# L-BAND_V2_0.net
KiCad netlist of a schematic drawn in Altium Designer
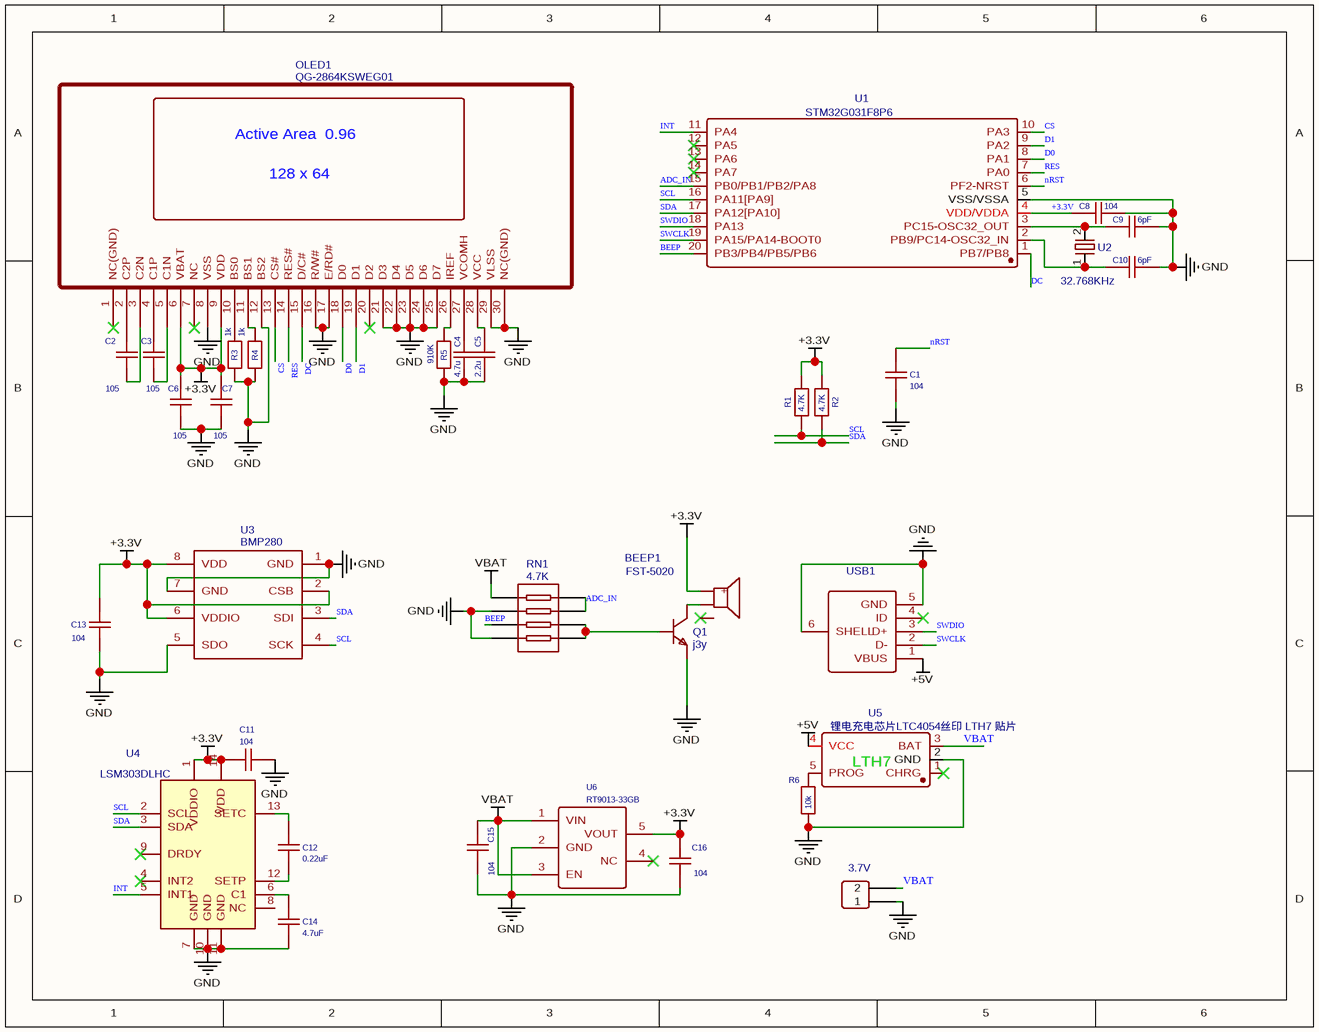
[diagram p0: L-BAND_V2_0.schdoc]

(export (version "E")
  (design (tool "Eeschema 10.0.6"))
  (components
    (comp (ref "3.7V")
      (value "3.7V 400mAH")
      (fields
        (field (name "BOM_MANUFACTURER PART") "2.54mm 1*2P")
        (field (name "BOM_SUPPLIER PART") "C36717")
      )
      (libsource (lib "altium-import") (part "root_2_3.7V 400mAH_"))
    )
    (comp (ref "BEEP1")
      (value "FST-5020")
      (fields (field (name "BOM_SUPPLIER PART") "C391029") (field (name "CONTRIBUTOR") "LCSC"))
      (libsource (lib "altium-import") (part "root_0_FST-5020_"))
    )
    (comp (ref "C1")
      (value "104")
      (fields (field (name "CONTRIBUTOR") "LCEDA_Lib"))
      (libsource (lib "altium-import") (part "root_1_104_"))
    )
    (comp (ref "C2")
      (value "105")
      (fields (field (name "CONTRIBUTOR") "LCEDA_Lib"))
      (libsource (lib "altium-import") (part "root_1_105_"))
    )
    (comp (ref "C3")
      (value "105")
      (fields (field (name "CONTRIBUTOR") "LCEDA_Lib"))
      (libsource (lib "altium-import") (part "root_1_105_"))
    )
    (comp (ref "C4")
      (value "4.7u")
      (fields (field (name "CONTRIBUTOR") "LCEDA_Lib"))
      (libsource (lib "altium-import") (part "root_1_4.7u_"))
    )
    (comp (ref "C5")
      (value "2.2u")
      (fields (field (name "CONTRIBUTOR") "LCEDA_Lib"))
      (libsource (lib "altium-import") (part "root_1_2.2u_"))
    )
    (comp (ref "C6")
      (value "105")
      (fields (field (name "CONTRIBUTOR") "LCEDA_Lib"))
      (libsource (lib "altium-import") (part "root_1_105_"))
    )
    (comp (ref "C7")
      (value "105")
      (fields (field (name "CONTRIBUTOR") "LCEDA_Lib"))
      (libsource (lib "altium-import") (part "root_1_105_"))
    )
    (comp (ref "C8")
      (value "104")
      (fields (field (name "CONTRIBUTOR") "LCEDA_Lib"))
      (libsource (lib "altium-import") (part "root_2_104_"))
    )
    (comp (ref "C9")
      (value "6pF")
      (fields (field (name "CONTRIBUTOR") "LCEDA_Lib"))
      (libsource (lib "altium-import") (part "root_2_6pF_"))
    )
    (comp (ref "C10")
      (value "6pF")
      (fields (field (name "CONTRIBUTOR") "LCEDA_Lib"))
      (libsource (lib "altium-import") (part "root_2_6pF_"))
    )
    (comp (ref "C11")
      (value "104")
      (fields (field (name "CONTRIBUTOR") "LCEDA_Lib"))
      (libsource (lib "altium-import") (part "root_2_104_"))
    )
    (comp (ref "C12")
      (value "0.22uF")
      (fields (field (name "CONTRIBUTOR") "LCEDA_Lib"))
      (libsource (lib "altium-import") (part "root_1_0.22uF_"))
    )
    (comp (ref "C13")
      (value "104")
      (fields (field (name "CONTRIBUTOR") "LCEDA_Lib"))
      (libsource (lib "altium-import") (part "root_1_104_"))
    )
    (comp (ref "C14")
      (value "4.7uF")
      (fields (field (name "CONTRIBUTOR") "LCEDA_Lib"))
      (libsource (lib "altium-import") (part "root_3_4.7uF_"))
    )
    (comp (ref "C15")
      (value "104")
      (fields (field (name "CONTRIBUTOR") "LCEDA_Lib"))
      (libsource (lib "altium-import") (part "root_1_104_"))
    )
    (comp (ref "C16")
      (value "104")
      (fields (field (name "CONTRIBUTOR") "LCEDA_Lib"))
      (libsource (lib "altium-import") (part "root_1_104_"))
    )
    (comp (ref "OLED1")
      (value "QG-2864KSWEG01")
      (fields (field (name "BOM_SUPPLIER PART") "C85007"))
      (libsource (lib "altium-import") (part "root_0_QG-2864KSWEG01_"))
    )
    (comp (ref "Q1")
      (value "j3y")
      (fields
        (field (name "BOM_SUPPLIER PART") "C364312")
        (field (name "BOM_MANUFACTURER PART") "S8050-J3Y")
        (field (name "CONTRIBUTOR") "youshutian")
      )
      (libsource (lib "altium-import") (part "root_0_j3y_"))
    )
    (comp (ref "R1")
      (value "4.7K")
      (fields (field (name "CONTRIBUTOR") "LCEDA_Lib"))
      (libsource (lib "altium-import") (part "root_3_4.7K_"))
    )
    (comp (ref "R2")
      (value "4.7K")
      (fields (field (name "CONTRIBUTOR") "LCEDA_Lib"))
      (libsource (lib "altium-import") (part "root_3_4.7K_"))
    )
    (comp (ref "R3")
      (value "1k")
      (fields (field (name "CONTRIBUTOR") "LCEDA_Lib"))
      (libsource (lib "altium-import") (part "root_3_1k_"))
    )
    (comp (ref "R4")
      (value "1k")
      (fields (field (name "CONTRIBUTOR") "LCEDA_Lib"))
      (libsource (lib "altium-import") (part "root_3_1k_"))
    )
    (comp (ref "R5")
      (value "910K")
      (fields (field (name "CONTRIBUTOR") "LCEDA_Lib"))
      (libsource (lib "altium-import") (part "root_3_910K_"))
    )
    (comp (ref "R6")
      (value "10k")
      (fields (field (name "CONTRIBUTOR") "LCEDA_Lib"))
      (libsource (lib "altium-import") (part "root_3_10k_"))
    )
    (comp (ref "RN1")
      (value "4.7K")
      (fields
        (field (name "BOM_MANUFACTURER PART") "RC-ML08W103JT")
        (field (name "BOM_SUPPLIER PART") "C69593")
        (field (name "CONTRIBUTOR") "LCSC")
      )
      (libsource (lib "altium-import") (part "root_1_4.7K_"))
    )
    (comp (ref "U1")
      (value "STM32G031F8P6")
      (fields (field (name "BOM_SUPPLIER PART") "C529334") (field (name "CONTRIBUTOR") "LCSC"))
      (libsource (lib "altium-import") (part "root_2_STM32G031F8P6_"))
    )
    (comp (ref "U2")
      (value "32.768KHz")
      (fields
        (field (name "BOM_SUPPLIER PART") "C1986919")
        (field (name "BOM_MANUFACTURER PART") "FC-135 32.7680KA-K0")
        (field (name "CONTRIBUTOR") "LCSC")
      )
      (libsource (lib "altium-import") (part "root_1_32.768KHz_"))
    )
    (comp (ref "U3")
      (value "BMP280")
      (fields (field (name "BOM_SUPPLIER PART") "C83291"))
      (libsource (lib "altium-import") (part "root_0_BMP280_"))
    )
    (comp (ref "U4")
      (value "LSM303DLHC")
      (fields (field (name "CONTRIBUTOR") "KiCAD"))
      (libsource (lib "altium-import") (part "root_0_LSM303DLHC_"))
    )
    (comp (ref "U5")
      (value "锂电充电芯片LTC4054丝印 LTH7 贴片")
      (fields
        (field (name "BOM_MANUFACTURER PART") "XT4054K421MR-G")
        (field (name "CONTRIBUTOR") "wudigaogao")
      )
      (libsource (lib "altium-import") (part "root_2_锂电充电芯片LTC4054丝印 LTH7 贴片_"))
    )
    (comp (ref "U6")
      (value "RT9013-33GB")
      (fields (field (name "BOM_SUPPLIER PART") "C47773"))
      (libsource (lib "altium-import") (part "root_0_RT9013-33GB_"))
    )
    (comp (ref "USB1")
      (value "MICRO XNJ ZB")
      (fields (field (name "BOM_SUPPLIER PART") "C668587") (field (name "CONTRIBUTOR") "LCSC"))
      (libsource (lib "altium-import") (part "root_2_MICRO XNJ ZB_"))
    )
  )
  (nets
    (net (code "1") (name "+3.3V") (class "Default")
      (node (ref "BEEP1") (pin "1") (pinfunction "+_1") (pintype "passive"))
      (node (ref "C11") (pin "2") (pinfunction "2_2") (pintype "passive"))
      (node (ref "C13") (pin "2") (pinfunction "2_2") (pintype "passive"))
      (node (ref "C16") (pin "2") (pinfunction "2_2") (pintype "passive"))
      (node (ref "C6") (pin "2") (pinfunction "2_2") (pintype "passive"))
      (node (ref "C7") (pin "2") (pinfunction "2_2") (pintype "passive"))
      (node (ref "C8") (pin "2") (pinfunction "2_2") (pintype "passive"))
      (node (ref "OLED1") (pin "6") (pinfunction "VBAT_6") (pintype "passive"))
      (node (ref "OLED1") (pin "9") (pinfunction "VDD_9") (pintype "passive"))
      (node (ref "R1") (pin "1") (pinfunction "1_1") (pintype "passive"))
      (node (ref "R2") (pin "1") (pinfunction "1_1") (pintype "passive"))
      (node (ref "U1") (pin "4") (pinfunction "VDD/VDDA_4") (pintype "passive"))
      (node (ref "U3") (pin "2") (pinfunction "CSB_2") (pintype "passive"))
      (node (ref "U3") (pin "6") (pinfunction "VDDIO_6") (pintype "passive"))
      (node (ref "U3") (pin "8") (pinfunction "VDD_8") (pintype "passive"))
      (node (ref "U4") (pin "1") (pinfunction "VDDIO_1") (pintype "passive"))
      (node (ref "U4") (pin "14") (pinfunction "VDD_14") (pintype "passive"))
      (node (ref "U6") (pin "5") (pinfunction "VOUT_5") (pintype "passive"))
    )
    (net (code "2") (name "+5V") (class "Default")
      (node (ref "U5") (pin "4") (pinfunction "VCC_4") (pintype "passive"))
      (node (ref "USB1") (pin "1") (pinfunction "VBUS_1") (pintype "passive"))
    )
    (net (code "3") (name "/ADC_IN") (class "Default")
      (node (ref "RN1") (pin "3") (pinfunction "3_3") (pintype "passive"))
      (node (ref "RN1") (pin "4") (pinfunction "4_4") (pintype "passive"))
      (node (ref "U1") (pin "15") (pinfunction "PB0/PB1/PB2/PA8_15") (pintype "passive"))
    )
    (net (code "4") (name "/BEEP") (class "Default")
      (node (ref "RN1") (pin "7") (pinfunction "7_7") (pintype "passive"))
      (node (ref "U1") (pin "20") (pinfunction "PB3/PB4/PB5/PB6_20") (pintype "passive"))
    )
    (net (code "5") (name "/CS") (class "Default")
      (node (ref "OLED1") (pin "13") (pinfunction "CS#_13") (pintype "passive"))
      (node (ref "U1") (pin "10") (pinfunction "PA3_10") (pintype "passive"))
    )
    (net (code "6") (name "/D0") (class "Default")
      (node (ref "OLED1") (pin "18") (pinfunction "D0_18") (pintype "passive"))
      (node (ref "U1") (pin "8") (pinfunction "PA1_8") (pintype "passive"))
    )
    (net (code "7") (name "/D1") (class "Default")
      (node (ref "OLED1") (pin "19") (pinfunction "D1_19") (pintype "passive"))
      (node (ref "U1") (pin "9") (pinfunction "PA2_9") (pintype "passive"))
    )
    (net (code "8") (name "/DC") (class "Default")
      (node (ref "OLED1") (pin "15") (pinfunction "D/C#_15") (pintype "passive"))
      (node (ref "U1") (pin "1") (pinfunction "PB7/PB8_1") (pintype "passive"))
    )
    (net (code "9") (name "/INT") (class "Default")
      (node (ref "U1") (pin "11") (pinfunction "PA4_11") (pintype "passive"))
      (node (ref "U4") (pin "5") (pinfunction "INT1_5") (pintype "passive"))
    )
    (net (code "10") (name "/RES") (class "Default")
      (node (ref "OLED1") (pin "14") (pinfunction "RES#_14") (pintype "passive"))
      (node (ref "U1") (pin "7") (pinfunction "PA0_7") (pintype "passive"))
    )
    (net (code "11") (name "/SCL") (class "Default")
      (node (ref "R1") (pin "2") (pinfunction "2_2") (pintype "passive"))
      (node (ref "U1") (pin "16") (pinfunction "PA11[PA9]_16") (pintype "passive"))
      (node (ref "U3") (pin "4") (pinfunction "SCK_4") (pintype "passive"))
      (node (ref "U4") (pin "2") (pinfunction "SCL_2") (pintype "passive"))
    )
    (net (code "12") (name "/SDA") (class "Default")
      (node (ref "R2") (pin "2") (pinfunction "2_2") (pintype "passive"))
      (node (ref "U1") (pin "17") (pinfunction "PA12[PA10]_17") (pintype "passive"))
      (node (ref "U3") (pin "3") (pinfunction "SDI_3") (pintype "passive"))
      (node (ref "U4") (pin "3") (pinfunction "SDA_3") (pintype "passive"))
    )
    (net (code "13") (name "/SWCLK") (class "Default")
      (node (ref "U1") (pin "19") (pinfunction "PA15/PA14-BOOT0_19") (pintype "passive"))
      (node (ref "USB1") (pin "2") (pinfunction "D-_2") (pintype "passive"))
    )
    (net (code "14") (name "/SWDIO") (class "Default")
      (node (ref "U1") (pin "18") (pinfunction "PA13_18") (pintype "passive"))
      (node (ref "USB1") (pin "3") (pinfunction "D+_3") (pintype "passive"))
    )
    (net (code "15") (name "/nRST") (class "Default")
      (node (ref "C1") (pin "2") (pinfunction "2_2") (pintype "passive"))
      (node (ref "U1") (pin "6") (pinfunction "PF2-NRST_6") (pintype "passive"))
    )
    (net (code "16") (name "GND") (class "Default")
      (node (ref "3.7V") (pin "1") (pinfunction "1_1") (pintype "passive"))
      (node (ref "C1") (pin "1") (pinfunction "1_1") (pintype "passive"))
      (node (ref "C10") (pin "1") (pinfunction "1_1") (pintype "passive"))
      (node (ref "C11") (pin "1") (pinfunction "1_1") (pintype "passive"))
      (node (ref "C13") (pin "1") (pinfunction "1_1") (pintype "passive"))
      (node (ref "C14") (pin "2") (pinfunction "2_2") (pintype "passive"))
      (node (ref "C15") (pin "1") (pinfunction "1_1") (pintype "passive"))
      (node (ref "C16") (pin "1") (pinfunction "1_1") (pintype "passive"))
      (node (ref "C4") (pin "1") (pinfunction "1_1") (pintype "passive"))
      (node (ref "C5") (pin "1") (pinfunction "1_1") (pintype "passive"))
      (node (ref "C6") (pin "1") (pinfunction "1_1") (pintype "passive"))
      (node (ref "C7") (pin "1") (pinfunction "1_1") (pintype "passive"))
      (node (ref "C8") (pin "1") (pinfunction "1_1") (pintype "passive"))
      (node (ref "C9") (pin "1") (pinfunction "1_1") (pintype "passive"))
      (node (ref "OLED1") (pin "12") (pinfunction "BS2_12") (pintype "passive"))
      (node (ref "OLED1") (pin "16") (pinfunction "R/W#_16") (pintype "passive"))
      (node (ref "OLED1") (pin "17") (pinfunction "E/RD#_17") (pintype "passive"))
      (node (ref "OLED1") (pin "21") (pinfunction "D3_21") (pintype "passive"))
      (node (ref "OLED1") (pin "22") (pinfunction "D4_22") (pintype "passive"))
      (node (ref "OLED1") (pin "23") (pinfunction "D5_23") (pintype "passive"))
      (node (ref "OLED1") (pin "24") (pinfunction "D6_24") (pintype "passive"))
      (node (ref "OLED1") (pin "25") (pinfunction "D7_25") (pintype "passive"))
      (node (ref "OLED1") (pin "29") (pinfunction "VLSS_29") (pintype "passive"))
      (node (ref "OLED1") (pin "30") (pinfunction "NC(GND)_30") (pintype "passive"))
      (node (ref "OLED1") (pin "8") (pinfunction "VSS_8") (pintype "passive"))
      (node (ref "Q1") (pin "2") (pinfunction "E_2") (pintype "passive"))
      (node (ref "R3") (pin "2") (pinfunction "2_2") (pintype "passive"))
      (node (ref "R4") (pin "2") (pinfunction "2_2") (pintype "passive"))
      (node (ref "R5") (pin "2") (pinfunction "2_2") (pintype "passive"))
      (node (ref "R6") (pin "2") (pinfunction "2_2") (pintype "passive"))
      (node (ref "RN1") (pin "6") (pinfunction "6_6") (pintype "passive"))
      (node (ref "RN1") (pin "8") (pinfunction "8_8") (pintype "passive"))
      (node (ref "U1") (pin "5") (pinfunction "VSS/VSSA_5") (pintype "passive"))
      (node (ref "U3") (pin "1") (pinfunction "GND_1") (pintype "passive"))
      (node (ref "U3") (pin "5") (pinfunction "SDO_5") (pintype "passive"))
      (node (ref "U3") (pin "7") (pinfunction "GND_7") (pintype "passive"))
      (node (ref "U4") (pin "10") (pinfunction "GND_10") (pintype "passive"))
      (node (ref "U4") (pin "11") (pinfunction "GND_11") (pintype "passive"))
      (node (ref "U4") (pin "7") (pinfunction "GND_7") (pintype "passive"))
      (node (ref "U5") (pin "2") (pinfunction "GND_2") (pintype "passive"))
      (node (ref "U6") (pin "2") (pinfunction "GND_2") (pintype "passive"))
      (node (ref "USB1") (pin "5") (pinfunction "GND_5") (pintype "passive"))
      (node (ref "USB1") (pin "6") (pinfunction "SHELL_6") (pintype "passive"))
    )
    (net (code "17") (name "Net-(OLED1-BS0)") (class "Default")
      (node (ref "OLED1") (pin "10") (pinfunction "BS0_10") (pintype "passive"))
      (node (ref "R3") (pin "1") (pinfunction "1_1") (pintype "passive"))
    )
    (net (code "18") (name "Net-(OLED1-BS1)") (class "Default")
      (node (ref "OLED1") (pin "11") (pinfunction "BS1_11") (pintype "passive"))
      (node (ref "R4") (pin "1") (pinfunction "1_1") (pintype "passive"))
    )
    (net (code "19") (name "Net-(OLED1-C1N)") (class "Default")
      (node (ref "C3") (pin "1") (pinfunction "1_1") (pintype "passive"))
      (node (ref "OLED1") (pin "5") (pinfunction "C1N_5") (pintype "passive"))
    )
    (net (code "20") (name "Net-(OLED1-C1P)") (class "Default")
      (node (ref "C3") (pin "2") (pinfunction "2_2") (pintype "passive"))
      (node (ref "OLED1") (pin "4") (pinfunction "C1P_4") (pintype "passive"))
    )
    (net (code "21") (name "Net-(OLED1-C2N)") (class "Default")
      (node (ref "C2") (pin "1") (pinfunction "1_1") (pintype "passive"))
      (node (ref "OLED1") (pin "3") (pinfunction "C2N_3") (pintype "passive"))
    )
    (net (code "22") (name "Net-(OLED1-C2P)") (class "Default")
      (node (ref "C2") (pin "2") (pinfunction "2_2") (pintype "passive"))
      (node (ref "OLED1") (pin "2") (pinfunction "C2P_2") (pintype "passive"))
    )
    (net (code "23") (name "Net-(OLED1-IREF)") (class "Default")
      (node (ref "OLED1") (pin "26") (pinfunction "IREF_26") (pintype "passive"))
      (node (ref "R5") (pin "1") (pinfunction "1_1") (pintype "passive"))
    )
    (net (code "24") (name "Net-(OLED1-VCC)") (class "Default")
      (node (ref "C5") (pin "2") (pinfunction "2_2") (pintype "passive"))
      (node (ref "OLED1") (pin "28") (pinfunction "VCC_28") (pintype "passive"))
    )
    (net (code "25") (name "Net-(OLED1-VCOMH)") (class "Default")
      (node (ref "C4") (pin "2") (pinfunction "2_2") (pintype "passive"))
      (node (ref "OLED1") (pin "27") (pinfunction "VCOMH_27") (pintype "passive"))
    )
    (net (code "26") (name "Net-(Q1-B)") (class "Default")
      (node (ref "Q1") (pin "1") (pinfunction "B_1") (pintype "passive"))
      (node (ref "RN1") (pin "1") (pinfunction "1_1") (pintype "passive"))
      (node (ref "RN1") (pin "2") (pinfunction "2_2") (pintype "passive"))
    )
    (net (code "27") (name "Net-(Q1-C)") (class "Default")
      (node (ref "BEEP1") (pin "2") (pinfunction "2_2") (pintype "passive"))
      (node (ref "Q1") (pin "3") (pinfunction "C_3") (pintype "passive"))
    )
    (net (code "28") (name "Net-(U1-PB9{slash}PC14-OSC32_IN)") (class "Default")
      (node (ref "C10") (pin "2") (pinfunction "2_2") (pintype "passive"))
      (node (ref "U1") (pin "2") (pinfunction "PB9/PC14-OSC32_IN_2") (pintype "passive"))
      (node (ref "U2") (pin "1") (pinfunction "1_1") (pintype "passive"))
    )
    (net (code "29") (name "Net-(U1-PC15-OSC32_OUT)") (class "Default")
      (node (ref "C9") (pin "2") (pinfunction "2_2") (pintype "passive"))
      (node (ref "U1") (pin "3") (pinfunction "PC15-OSC32_OUT_3") (pintype "passive"))
      (node (ref "U2") (pin "2") (pinfunction "GND_2") (pintype "passive"))
    )
    (net (code "30") (name "Net-(U4-C1)") (class "Default")
      (node (ref "C14") (pin "1") (pinfunction "1_1") (pintype "passive"))
      (node (ref "U4") (pin "6") (pinfunction "C1_6") (pintype "passive"))
    )
    (net (code "31") (name "Net-(U4-SETC)") (class "Default")
      (node (ref "C12") (pin "2") (pinfunction "2_2") (pintype "passive"))
      (node (ref "U4") (pin "13") (pinfunction "SETC_13") (pintype "passive"))
    )
    (net (code "32") (name "Net-(U4-SETP)") (class "Default")
      (node (ref "C12") (pin "1") (pinfunction "1_1") (pintype "passive"))
      (node (ref "U4") (pin "12") (pinfunction "SETP_12") (pintype "passive"))
    )
    (net (code "33") (name "Net-(U5-PROG)") (class "Default")
      (node (ref "R6") (pin "1") (pinfunction "1_1") (pintype "passive"))
      (node (ref "U5") (pin "5") (pinfunction "PROG_5") (pintype "passive"))
    )
    (net (code "34") (name "VBAT") (class "Default")
      (node (ref "3.7V") (pin "2") (pinfunction "2_2") (pintype "passive"))
      (node (ref "C15") (pin "2") (pinfunction "2_2") (pintype "passive"))
      (node (ref "RN1") (pin "5") (pinfunction "5_5") (pintype "passive"))
      (node (ref "U5") (pin "3") (pinfunction "BAT_3") (pintype "passive"))
      (node (ref "U6") (pin "1") (pinfunction "VIN_1") (pintype "passive"))
      (node (ref "U6") (pin "3") (pinfunction "EN_3") (pintype "passive"))
    )
    (net (code "35") (name "unconnected-(BEEP1-Pad3)") (class "Default")
      (node (ref "BEEP1") (pin "3") (pinfunction "3_3") (pintype "passive+no_connect"))
    )
    (net (code "36") (name "unconnected-(OLED1-D2-Pad20)") (class "Default")
      (node (ref "OLED1") (pin "20") (pinfunction "D2_20") (pintype "passive+no_connect"))
    )
    (net (code "37") (name "unconnected-(OLED1-NC(GND)-Pad1)") (class "Default")
      (node (ref "OLED1") (pin "1") (pinfunction "NC(GND)_1") (pintype "passive+no_connect"))
    )
    (net (code "38") (name "unconnected-(OLED1-NC-Pad7)") (class "Default")
      (node (ref "OLED1") (pin "7") (pinfunction "NC_7") (pintype "passive+no_connect"))
    )
    (net (code "39") (name "unconnected-(U1-PA5-Pad12)") (class "Default")
      (node (ref "U1") (pin "12") (pinfunction "PA5_12") (pintype "passive+no_connect"))
    )
    (net (code "40") (name "unconnected-(U1-PA6-Pad13)") (class "Default")
      (node (ref "U1") (pin "13") (pinfunction "PA6_13") (pintype "passive+no_connect"))
    )
    (net (code "41") (name "unconnected-(U1-PA7-Pad14)") (class "Default")
      (node (ref "U1") (pin "14") (pinfunction "PA7_14") (pintype "passive+no_connect"))
    )
    (net (code "42") (name "unconnected-(U4-DRDY-Pad9)") (class "Default")
      (node (ref "U4") (pin "9") (pinfunction "DRDY_9") (pintype "passive+no_connect"))
    )
    (net (code "43") (name "unconnected-(U4-INT2-Pad4)") (class "Default")
      (node (ref "U4") (pin "4") (pinfunction "INT2_4") (pintype "passive+no_connect"))
    )
    (net (code "44") (name "unconnected-(U4-NC-Pad8)") (class "Default")
      (node (ref "U4") (pin "8") (pinfunction "NC_8") (pintype "passive"))
    )
    (net (code "45") (name "unconnected-(U5-CHRG-Pad1)") (class "Default")
      (node (ref "U5") (pin "1") (pinfunction "CHRG_1") (pintype "passive+no_connect"))
    )
    (net (code "46") (name "unconnected-(U6-NC-Pad4)") (class "Default")
      (node (ref "U6") (pin "4") (pinfunction "NC_4") (pintype "passive+no_connect"))
    )
    (net (code "47") (name "unconnected-(USB1-ID-Pad4)") (class "Default")
      (node (ref "USB1") (pin "4") (pinfunction "ID_4") (pintype "passive+no_connect"))
    )
  )
)
